# RemoteControl.net
KiCad netlist of a schematic drawn in Altium Designer
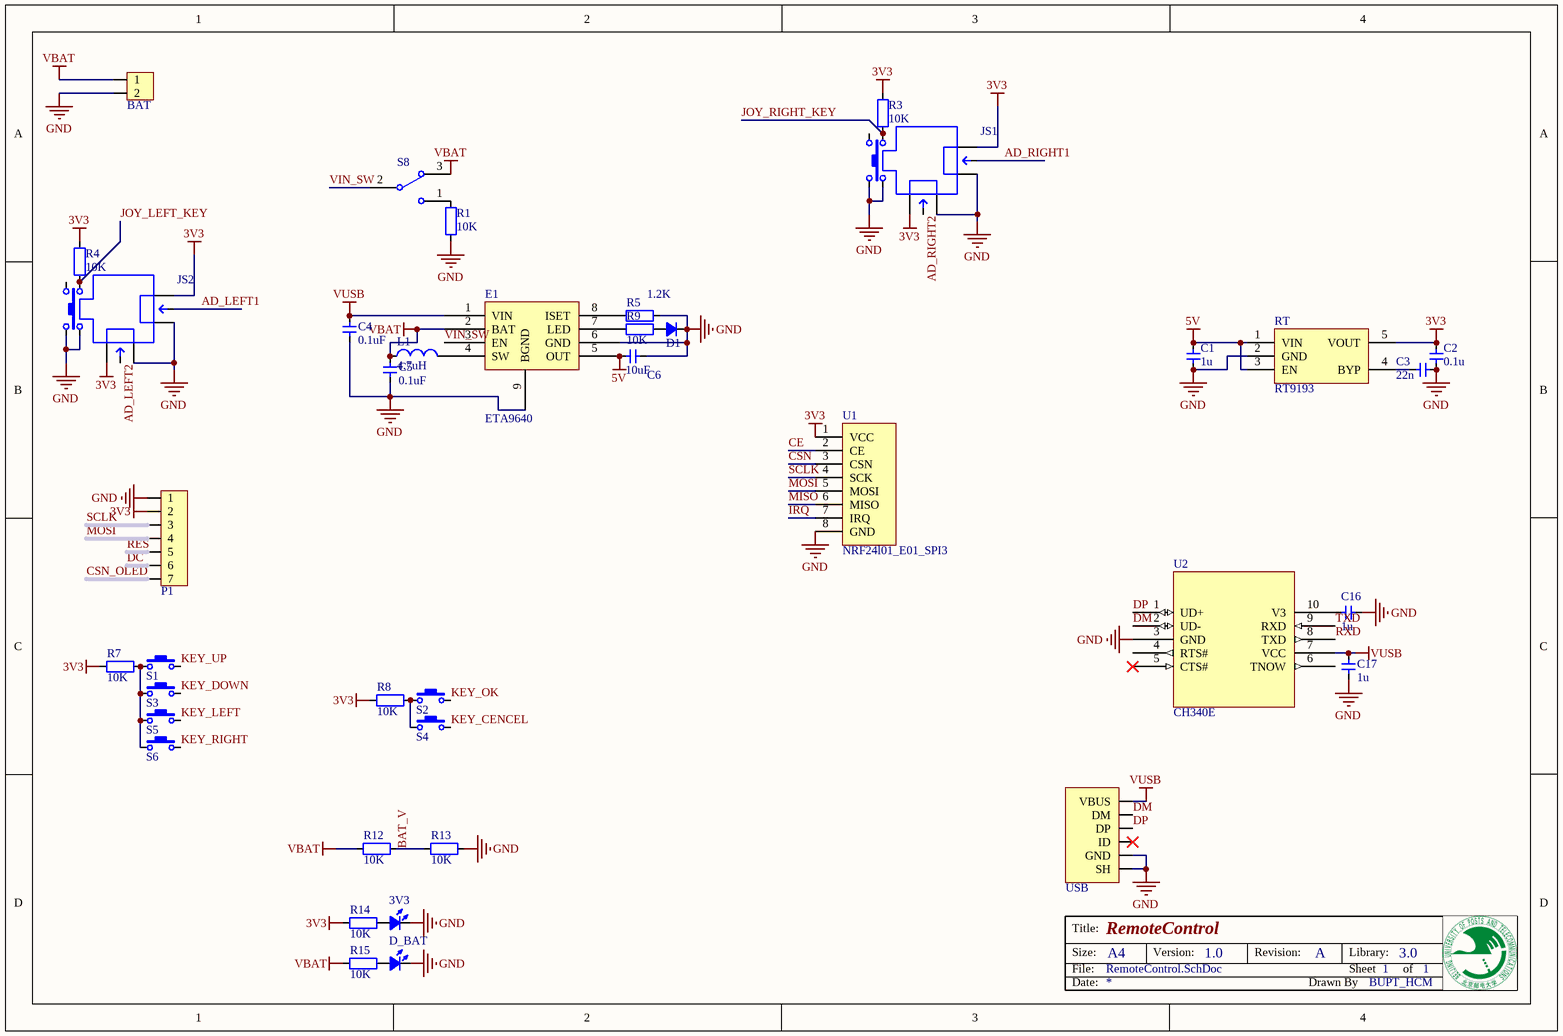
[diagram p0: RemoteControl.SchDoc]

(export (version "E")
  (design (tool "Eeschema 10.0.6"))
  (components
    (comp (ref "3V3")
      (value "LED_0805")
      (footprint "PCB_ActiveLED:LED_0805_RED")
      (description "LED")
      (libsource (lib "SCH_Active") (part "LED_0805"))
    )
    (comp (ref "BAT")
      (value "HDR1x2_2.54")
      (footprint "PCB_ConnectorHDR:HDR1X2_2.54_90")
      (description "Header")
      (libsource (lib "SCH_ConnectorHDR") (part "HDR1x2_2.54"))
    )
    (comp (ref "C1")
      (value "1u")
      (footprint "PCB_PassiveCap:CAP_0603")
      (description "Capacitor")
      (fields (field (name "Comment") "Cap_0603"))
      (libsource (lib "SCH_Passive") (part "Cap_0603"))
    )
    (comp (ref "C2")
      (value "0.1u")
      (footprint "PCB_PassiveCap:CAP_0603")
      (description "Capacitor")
      (fields (field (name "Comment") "Cap_0603"))
      (libsource (lib "SCH_Passive") (part "Cap_0603"))
    )
    (comp (ref "C3")
      (value "22n")
      (footprint "PCB_PassiveCap:CAP_0603")
      (description "Capacitor")
      (fields (field (name "Comment") "Cap_0603"))
      (libsource (lib "SCH_Passive") (part "Cap_0603"))
    )
    (comp (ref "C4")
      (value "0.1uF")
      (footprint "PCB_PassiveCap:CAP_0603")
      (description "Capacitor")
      (fields (field (name "Comment") "Cap_0603"))
      (libsource (lib "SCH_Passive") (part "Cap_0603"))
    )
    (comp (ref "C5")
      (value "0.1uF")
      (footprint "PCB_PassiveCap:CAP_0603")
      (description "Capacitor")
      (fields (field (name "Comment") "Cap_0603"))
      (libsource (lib "SCH_Passive") (part "Cap_0603"))
    )
    (comp (ref "C6")
      (value "10uF")
      (footprint "PCB_PassiveCap:CAP_0603")
      (description "Capacitor")
      (fields (field (name "Comment") "Cap_0603"))
      (libsource (lib "SCH_Passive") (part "Cap_0603"))
    )
    (comp (ref "C16")
      (value "1u")
      (footprint "PCB_PassiveCap:CAP_0603")
      (description "Capacitor")
      (fields (field (name "Comment") "Cap_0603"))
      (libsource (lib "SCH_Passive") (part "Cap_0603"))
    )
    (comp (ref "C17")
      (value "1u")
      (footprint "PCB_PassiveCap:CAP_0603")
      (description "Capacitor")
      (fields (field (name "Comment") "Cap_0603"))
      (libsource (lib "SCH_Passive") (part "Cap_0603"))
    )
    (comp (ref "D1")
      (value "D_0805")
      (footprint "LED_0805_YELLOW")
      (libsource (lib "SCH_Active") (part "D_0805"))
    )
    (comp (ref "D_BAT")
      (value "LED_0805")
      (footprint "PCB_ActiveLED:LED_0805_RED")
      (description "LED")
      (libsource (lib "SCH_Active") (part "LED_0805"))
    )
    (comp (ref "E1")
      (value "ETA9640")
      (footprint "SOP_E150_8 -with_PADs")
      (libsource (lib "SCH_IntegratedCircuit") (part "ETA9640"))
    )
    (comp (ref "JS1")
      (value "JoyStick")
      (footprint "PCB_Switch:JoyStick")
      (libsource (lib "SCH_Switch") (part "JoyStick"))
    )
    (comp (ref "JS2")
      (value "JoyStick")
      (footprint "PCB_Switch:JoyStick")
      (libsource (lib "SCH_Switch") (part "JoyStick"))
    )
    (comp (ref "L1")
      (value "4.7uH")
      (footprint "PCB_PassiveInd:IND_CD32")
      (description "Inductor")
      (fields (field (name "Comment") "Ind_CD32"))
      (libsource (lib "SCH_Passive") (part "Ind_CD32"))
    )
    (comp (ref "P1")
      (value "HDR1x7_2.54")
      (footprint "PCB_ConnectorHDR:HDR1X7_2.54_180")
      (description "Header")
      (libsource (lib "SCH_ConnectorHDR") (part "HDR1x7_2.54T"))
    )
    (comp (ref "R1")
      (value "10K")
      (footprint "PCB_PassiveRes:RES_0603")
      (description "Resistor")
      (fields (field (name "Comment") "Res_0603"))
      (libsource (lib "SCH_Passive") (part "Res_0603"))
    )
    (comp (ref "R3")
      (value "10K")
      (footprint "PCB_PassiveRes:RES_0603")
      (description "Resistor")
      (fields (field (name "Comment") "Res_0603"))
      (libsource (lib "SCH_Passive") (part "Res_0603"))
    )
    (comp (ref "R4")
      (value "10K")
      (footprint "PCB_PassiveRes:RES_0603")
      (description "Resistor")
      (fields (field (name "Comment") "Res_0603"))
      (libsource (lib "SCH_Passive") (part "Res_0603"))
    )
    (comp (ref "R5")
      (value "1.2K")
      (footprint "PCB_PassiveRes:RES_0603")
      (description "Resistor")
      (fields (field (name "Comment") "Res_0603"))
      (libsource (lib "") (part "Res_0603_1"))
    )
    (comp (ref "R7")
      (value "10K")
      (footprint "PCB_PassiveRes:RES_0603")
      (description "Resistor")
      (fields (field (name "Comment") "Res_0603"))
      (libsource (lib "") (part "Res_0603_1"))
    )
    (comp (ref "R8")
      (value "10K")
      (footprint "PCB_PassiveRes:RES_0603")
      (description "Resistor")
      (fields (field (name "Comment") "Res_0603"))
      (libsource (lib "") (part "Res_0603_1"))
    )
    (comp (ref "R9")
      (value "10K")
      (footprint "PCB_PassiveRes:RES_0603")
      (description "Resistor")
      (fields (field (name "Comment") "Res_0603"))
      (libsource (lib "") (part "Res_0603_1"))
    )
    (comp (ref "R12")
      (value "10K")
      (footprint "PCB_PassiveRes:RES_0603")
      (description "Resistor")
      (fields (field (name "Comment") "Res_0603"))
      (libsource (lib "") (part "Res_0603_1"))
    )
    (comp (ref "R13")
      (value "10K")
      (footprint "PCB_PassiveRes:RES_0603")
      (description "Resistor")
      (fields (field (name "Comment") "Res_0603"))
      (libsource (lib "") (part "Res_0603_1"))
    )
    (comp (ref "R14")
      (value "10K")
      (footprint "PCB_PassiveRes:RES_0603")
      (description "Resistor")
      (fields (field (name "Comment") "Res_0603"))
      (libsource (lib "") (part "Res_0603_2"))
    )
    (comp (ref "R15")
      (value "10K")
      (footprint "PCB_PassiveRes:RES_0603")
      (description "Resistor")
      (fields (field (name "Comment") "Res_0603"))
      (libsource (lib "") (part "Res_0603_2"))
    )
    (comp (ref "RT")
      (value "RT9193")
      (footprint "PCB_IntegratedCircuit:SOT23-5")
      (description "Power")
      (libsource (lib "SCH_IntegratedCircuit") (part "RT9193"))
    )
    (comp (ref "S1")
      (value "ButtonTACT_3x6x2.5_180")
      (footprint "PCB_Switch:ButtonTACT_3x6x2.5_180")
      (description "Button")
      (libsource (lib "SCH_Switch") (part "ButtonTACT_3x6x2.5_180"))
    )
    (comp (ref "S2")
      (value "ButtonTACT_3x6x2.5_180")
      (footprint "PCB_Switch:ButtonTACT_3x6x2.5_180")
      (description "Button")
      (libsource (lib "SCH_Switch") (part "ButtonTACT_3x6x2.5_180"))
    )
    (comp (ref "S3")
      (value "ButtonTACT_3x6x2.5_180")
      (footprint "PCB_Switch:ButtonTACT_3x6x2.5_180")
      (description "Button")
      (libsource (lib "SCH_Switch") (part "ButtonTACT_3x6x2.5_180"))
    )
    (comp (ref "S4")
      (value "ButtonTACT_3x6x2.5_180")
      (footprint "PCB_Switch:ButtonTACT_3x6x2.5_180")
      (description "Button")
      (libsource (lib "SCH_Switch") (part "ButtonTACT_3x6x2.5_180"))
    )
    (comp (ref "S5")
      (value "ButtonTACT_3x6x2.5_180")
      (footprint "PCB_Switch:ButtonTACT_3x6x2.5_180")
      (description "Button")
      (libsource (lib "SCH_Switch") (part "ButtonTACT_3x6x2.5_180"))
    )
    (comp (ref "S6")
      (value "ButtonTACT_3x6x2.5_180")
      (footprint "PCB_Switch:ButtonTACT_3x6x2.5_180")
      (description "Button")
      (libsource (lib "SCH_Switch") (part "ButtonTACT_3x6x2.5_180"))
    )
    (comp (ref "S8")
      (value "SwitchSPDT_2.8x6.6_90")
      (footprint "PCB_Switch:SwitchSPDT_2.8X6.6_90")
      (description "Switch")
      (libsource (lib "SCH_Switch") (part "SwitchSPDT_2.8x6.6_90"))
    )
    (comp (ref "U1")
      (value "NRF24l01_E01_SPI3")
      (footprint "E01-ML01SP2")
      (libsource (lib "SCH_Module") (part "NRF24l01_E01_SPI2"))
    )
    (comp (ref "U2")
      (value "CH340E")
      (footprint "MSOP10")
      (description "USB to TTL Serial / UART")
      (libsource (lib "*") (part "CH340E"))
    )
    (comp (ref "USB")
      (value "USB_Micro")
      (footprint "PCB_USB:USB_Micro-AB")
      (description "USB")
      (libsource (lib "SCH_USB") (part "USB_Micro"))
    )
  )
  (nets
    (net (code "1") (name "/AD_LEFT1") (class "Default")
      (node (ref "JS2") (pin "5") (pinfunction "5_5") (pintype "passive"))
    )
    (net (code "2") (name "/AD_LEFT2") (class "Default")
      (node (ref "JS2") (pin "2") (pinfunction "2_2") (pintype "passive"))
    )
    (net (code "3") (name "/AD_RIGHT1") (class "Default")
      (node (ref "JS1") (pin "5") (pinfunction "5_5") (pintype "passive"))
    )
    (net (code "4") (name "/AD_RIGHT2") (class "Default")
      (node (ref "JS1") (pin "2") (pinfunction "2_2") (pintype "passive"))
    )
    (net (code "5") (name "/BAT_V") (class "Default")
      (node (ref "R12") (pin "1") (pinfunction "1_1") (pintype "passive"))
      (node (ref "R13") (pin "2") (pinfunction "2_2") (pintype "passive"))
    )
    (net (code "6") (name "/CE") (class "Default")
      (node (ref "U1") (pin "2") (pinfunction "CE_2") (pintype "passive"))
    )
    (net (code "7") (name "/CSN") (class "Default")
      (node (ref "U1") (pin "3") (pinfunction "CSN_3") (pintype "passive"))
    )
    (net (code "8") (name "/CSN_OLED") (class "Default")
      (node (ref "P1") (pin "7") (pinfunction "7_7") (pintype "passive"))
    )
    (net (code "9") (name "/DC") (class "Default")
      (node (ref "P1") (pin "6") (pinfunction "6_6") (pintype "passive"))
    )
    (net (code "10") (name "/DM") (class "Default")
      (node (ref "U2") (pin "2") (pinfunction "UD-_2") (pintype "bidirectional"))
      (node (ref "USB") (pin "2") (pinfunction "DM_2") (pintype "passive"))
    )
    (net (code "11") (name "/DP") (class "Default")
      (node (ref "U2") (pin "1") (pinfunction "UD+_1") (pintype "bidirectional"))
      (node (ref "USB") (pin "3") (pinfunction "DP_3") (pintype "passive"))
    )
    (net (code "12") (name "/IRQ") (class "Default")
      (node (ref "U1") (pin "7") (pinfunction "IRQ_7") (pintype "passive"))
    )
    (net (code "13") (name "/JOY_LEFT_KEY") (class "Default")
      (node (ref "JS2") (pin "9") (pinfunction "9_9") (pintype "passive"))
      (node (ref "R4") (pin "1") (pinfunction "1_1") (pintype "passive"))
    )
    (net (code "14") (name "/JOY_RIGHT_KEY") (class "Default")
      (node (ref "JS1") (pin "9") (pinfunction "9_9") (pintype "passive"))
      (node (ref "R3") (pin "1") (pinfunction "1_1") (pintype "passive"))
    )
    (net (code "15") (name "/KEY_CENCEL") (class "Default")
      (node (ref "S4") (pin "2") (pinfunction "2_2") (pintype "passive"))
    )
    (net (code "16") (name "/KEY_DOWN") (class "Default")
      (node (ref "S3") (pin "2") (pinfunction "2_2") (pintype "passive"))
    )
    (net (code "17") (name "/KEY_LEFT") (class "Default")
      (node (ref "S5") (pin "2") (pinfunction "2_2") (pintype "passive"))
    )
    (net (code "18") (name "/KEY_OK") (class "Default")
      (node (ref "S2") (pin "2") (pinfunction "2_2") (pintype "passive"))
    )
    (net (code "19") (name "/KEY_RIGHT") (class "Default")
      (node (ref "S6") (pin "2") (pinfunction "2_2") (pintype "passive"))
    )
    (net (code "20") (name "/KEY_UP") (class "Default")
      (node (ref "S1") (pin "2") (pinfunction "2_2") (pintype "passive"))
    )
    (net (code "21") (name "/MISO") (class "Default")
      (node (ref "U1") (pin "6") (pinfunction "MISO_6") (pintype "passive"))
    )
    (net (code "22") (name "/MOSI") (class "Default")
      (node (ref "P1") (pin "4") (pinfunction "4_4") (pintype "passive"))
      (node (ref "U1") (pin "5") (pinfunction "MOSI_5") (pintype "passive"))
    )
    (net (code "23") (name "/RES") (class "Default")
      (node (ref "P1") (pin "5") (pinfunction "5_5") (pintype "passive"))
    )
    (net (code "24") (name "/RXD") (class "Default")
      (node (ref "U2") (pin "8") (pinfunction "TXD_8") (pintype "output"))
    )
    (net (code "25") (name "/SCLK") (class "Default")
      (node (ref "P1") (pin "3") (pinfunction "3_3") (pintype "passive"))
      (node (ref "U1") (pin "4") (pinfunction "SCK_4") (pintype "passive"))
    )
    (net (code "26") (name "/TXD") (class "Default")
      (node (ref "U2") (pin "9") (pinfunction "RXD_9") (pintype "input"))
    )
    (net (code "27") (name "/VIN_SW") (class "Default")
      (node (ref "E1") (pin "3") (pinfunction "EN_3") (pintype "passive"))
      (node (ref "S8") (pin "2") (pinfunction "2_2") (pintype "passive"))
    )
    (net (code "28") (name "3V3") (class "Default")
      (node (ref "C2") (pin "2") (pinfunction "2_2") (pintype "passive"))
      (node (ref "JS1") (pin "1") (pinfunction "1_1") (pintype "passive"))
      (node (ref "JS1") (pin "6") (pinfunction "6_6") (pintype "passive"))
      (node (ref "JS2") (pin "1") (pinfunction "1_1") (pintype "passive"))
      (node (ref "JS2") (pin "6") (pinfunction "6_6") (pintype "passive"))
      (node (ref "P1") (pin "2") (pinfunction "2_2") (pintype "passive"))
      (node (ref "R14") (pin "1") (pinfunction "1_1") (pintype "passive"))
      (node (ref "R3") (pin "2") (pinfunction "2_2") (pintype "passive"))
      (node (ref "R4") (pin "2") (pinfunction "2_2") (pintype "passive"))
      (node (ref "R7") (pin "2") (pinfunction "2_2") (pintype "passive"))
      (node (ref "R8") (pin "2") (pinfunction "2_2") (pintype "passive"))
      (node (ref "RT") (pin "5") (pinfunction "VOUT_5") (pintype "passive"))
      (node (ref "U1") (pin "1") (pinfunction "VCC_1") (pintype "passive"))
    )
    (net (code "29") (name "5V") (class "Default")
      (node (ref "C1") (pin "2") (pinfunction "2_2") (pintype "passive"))
      (node (ref "C6") (pin "1") (pinfunction "1_1") (pintype "passive"))
      (node (ref "E1") (pin "5") (pinfunction "OUT_5") (pintype "passive"))
      (node (ref "RT") (pin "1") (pinfunction "VIN_1") (pintype "passive"))
      (node (ref "RT") (pin "3") (pinfunction "EN_3") (pintype "power_in"))
    )
    (net (code "30") (name "GND") (class "Default")
      (node (ref "3V3") (pin "2") (pinfunction "K_2") (pintype "passive"))
      (node (ref "BAT") (pin "2") (pinfunction "2_2") (pintype "passive"))
      (node (ref "C1") (pin "1") (pinfunction "1_1") (pintype "passive"))
      (node (ref "C16") (pin "1") (pinfunction "1_1") (pintype "passive"))
      (node (ref "C17") (pin "2") (pinfunction "2_2") (pintype "passive"))
      (node (ref "C2") (pin "1") (pinfunction "1_1") (pintype "passive"))
      (node (ref "C3") (pin "1") (pinfunction "1_1") (pintype "passive"))
      (node (ref "C4") (pin "2") (pinfunction "2_2") (pintype "passive"))
      (node (ref "C5") (pin "2") (pinfunction "2_2") (pintype "passive"))
      (node (ref "C6") (pin "2") (pinfunction "2_2") (pintype "passive"))
      (node (ref "D1") (pin "2") (pinfunction "K_2") (pintype "passive"))
      (node (ref "D_BAT") (pin "2") (pinfunction "K_2") (pintype "passive"))
      (node (ref "E1") (pin "6") (pinfunction "GND_6") (pintype "passive"))
      (node (ref "E1") (pin "9") (pinfunction "BGND_9") (pintype "passive"))
      (node (ref "JS1") (pin "10") (pinfunction "10_10") (pintype "passive"))
      (node (ref "JS1") (pin "3") (pinfunction "3_3") (pintype "passive"))
      (node (ref "JS1") (pin "4") (pinfunction "4_4") (pintype "passive"))
      (node (ref "JS1") (pin "8") (pinfunction "8_8") (pintype "passive"))
      (node (ref "JS2") (pin "10") (pinfunction "10_10") (pintype "passive"))
      (node (ref "JS2") (pin "3") (pinfunction "3_3") (pintype "passive"))
      (node (ref "JS2") (pin "4") (pinfunction "4_4") (pintype "passive"))
      (node (ref "JS2") (pin "8") (pinfunction "8_8") (pintype "passive"))
      (node (ref "P1") (pin "1") (pinfunction "1_1") (pintype "passive"))
      (node (ref "R1") (pin "1") (pinfunction "1_1") (pintype "passive"))
      (node (ref "R13") (pin "1") (pinfunction "1_1") (pintype "passive"))
      (node (ref "R5") (pin "1") (pinfunction "1_1") (pintype "passive"))
      (node (ref "RT") (pin "2") (pinfunction "GND_2") (pintype "passive"))
      (node (ref "U1") (pin "8") (pinfunction "GND_8") (pintype "passive"))
      (node (ref "U2") (pin "3") (pinfunction "GND_3") (pintype "power_in"))
      (node (ref "USB") (pin "0") (pinfunction "SH_0") (pintype "passive"))
      (node (ref "USB") (pin "5") (pinfunction "GND_5") (pintype "passive"))
    )
    (net (code "31") (name "Net-(3V3-A)") (class "Default")
      (node (ref "3V3") (pin "1") (pinfunction "A_1") (pintype "passive"))
      (node (ref "R14") (pin "2") (pinfunction "2_2") (pintype "passive"))
    )
    (net (code "32") (name "Net-(D1-A)") (class "Default")
      (node (ref "D1") (pin "1") (pinfunction "A_1") (pintype "passive"))
      (node (ref "R9") (pin "1") (pinfunction "1_1") (pintype "passive"))
    )
    (net (code "33") (name "Net-(D_BAT-A)") (class "Default")
      (node (ref "D_BAT") (pin "1") (pinfunction "A_1") (pintype "passive"))
      (node (ref "R15") (pin "2") (pinfunction "2_2") (pintype "passive"))
    )
    (net (code "34") (name "Net-(E1-ISET)") (class "Default")
      (node (ref "E1") (pin "8") (pinfunction "ISET_8") (pintype "passive"))
      (node (ref "R5") (pin "2") (pinfunction "2_2") (pintype "passive"))
    )
    (net (code "35") (name "Net-(E1-LED)") (class "Default")
      (node (ref "E1") (pin "7") (pinfunction "LED_7") (pintype "passive"))
      (node (ref "R9") (pin "2") (pinfunction "2_2") (pintype "passive"))
    )
    (net (code "36") (name "Net-(E1-SW)") (class "Default")
      (node (ref "E1") (pin "4") (pinfunction "SW_4") (pintype "passive"))
      (node (ref "L1") (pin "2") (pinfunction "2_2") (pintype "passive"))
    )
    (net (code "37") (name "Net-(R1-Pad2)") (class "Default")
      (node (ref "R1") (pin "2") (pinfunction "2_2") (pintype "passive"))
      (node (ref "S8") (pin "1") (pinfunction "1_1") (pintype "passive"))
    )
    (net (code "38") (name "Net-(R7-Pad1)") (class "Default")
      (node (ref "R7") (pin "1") (pinfunction "1_1") (pintype "passive"))
      (node (ref "S1") (pin "1") (pinfunction "1_1") (pintype "passive"))
      (node (ref "S3") (pin "1") (pinfunction "1_1") (pintype "passive"))
      (node (ref "S5") (pin "1") (pinfunction "1_1") (pintype "passive"))
      (node (ref "S6") (pin "1") (pinfunction "1_1") (pintype "passive"))
    )
    (net (code "39") (name "Net-(R8-Pad1)") (class "Default")
      (node (ref "R8") (pin "1") (pinfunction "1_1") (pintype "passive"))
      (node (ref "S2") (pin "1") (pinfunction "1_1") (pintype "passive"))
      (node (ref "S4") (pin "1") (pinfunction "1_1") (pintype "passive"))
    )
    (net (code "40") (name "Net-(RT-BYP)") (class "Default")
      (node (ref "C3") (pin "2") (pinfunction "2_2") (pintype "passive"))
      (node (ref "RT") (pin "4") (pinfunction "BYP_4") (pintype "passive"))
    )
    (net (code "41") (name "Net-(U2-V3)") (class "Default")
      (node (ref "C16") (pin "2") (pinfunction "2_2") (pintype "passive"))
      (node (ref "U2") (pin "10") (pinfunction "V3_10") (pintype "power_in"))
    )
    (net (code "42") (name "VBAT") (class "Default")
      (node (ref "BAT") (pin "1") (pinfunction "1_1") (pintype "passive"))
      (node (ref "C5") (pin "1") (pinfunction "1_1") (pintype "passive"))
      (node (ref "E1") (pin "2") (pinfunction "BAT_2") (pintype "passive"))
      (node (ref "L1") (pin "1") (pinfunction "1_1") (pintype "passive"))
      (node (ref "R12") (pin "2") (pinfunction "2_2") (pintype "passive"))
      (node (ref "R15") (pin "1") (pinfunction "1_1") (pintype "passive"))
      (node (ref "S8") (pin "3") (pinfunction "3_3") (pintype "passive"))
    )
    (net (code "43") (name "VUSB") (class "Default")
      (node (ref "C17") (pin "1") (pinfunction "1_1") (pintype "passive"))
      (node (ref "C4") (pin "1") (pinfunction "1_1") (pintype "passive"))
      (node (ref "E1") (pin "1") (pinfunction "VIN_1") (pintype "passive"))
      (node (ref "U2") (pin "7") (pinfunction "VCC_7") (pintype "power_in"))
      (node (ref "USB") (pin "1") (pinfunction "VBUS_1") (pintype "passive"))
    )
    (net (code "44") (name "unconnected-(JS1-Pad7)") (class "Default")
      (node (ref "JS1") (pin "7") (pinfunction "7_7") (pintype "passive"))
    )
    (net (code "45") (name "unconnected-(JS2-Pad7)") (class "Default")
      (node (ref "JS2") (pin "7") (pinfunction "7_7") (pintype "passive"))
    )
    (net (code "46") (name "unconnected-(U2-CTS#-Pad5)") (class "Default")
      (node (ref "U2") (pin "5") (pinfunction "CTS#_5") (pintype "input+no_connect"))
    )
    (net (code "47") (name "unconnected-(U2-RTS#-Pad4)") (class "Default")
      (node (ref "U2") (pin "4") (pinfunction "RTS#_4") (pintype "output"))
    )
    (net (code "48") (name "unconnected-(U2-TNOW-Pad6)") (class "Default")
      (node (ref "U2") (pin "6") (pinfunction "TNOW_6") (pintype "output"))
    )
    (net (code "49") (name "unconnected-(USB-ID-Pad4)") (class "Default")
      (node (ref "USB") (pin "4") (pinfunction "ID_4") (pintype "passive+no_connect"))
    )
  )
)
